# bt-programmer.net
KiCad netlist of a schematic drawn in EAGLE
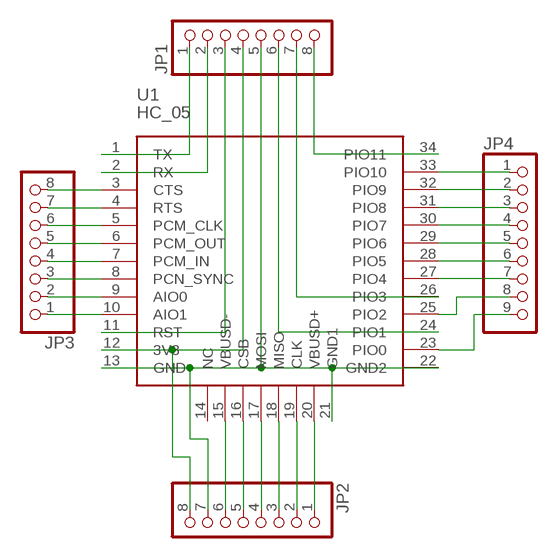
[diagram p0: schematic, sheet 1]

(export (version "E")
  (design (tool "Eeschema 10.0.6"))
  (components
    (comp (ref "JP1")
      (value "PINHD-1X8")
      (footprint "eagle-import:1X08")
      (libsource (lib "eagle-import") (part "PINHD-1X8"))
    )
    (comp (ref "JP2")
      (value "PINHD-1X8")
      (footprint "eagle-import:1X08")
      (libsource (lib "eagle-import") (part "PINHD-1X8"))
    )
    (comp (ref "JP3")
      (value "PINHD-1X8")
      (footprint "eagle-import:1X08")
      (libsource (lib "eagle-import") (part "PINHD-1X8"))
    )
    (comp (ref "JP4")
      (value "PINHD-1X9")
      (footprint "eagle-import:1X09")
      (libsource (lib "eagle-import") (part "PINHD-1X9"))
    )
    (comp (ref "U1")
      (value "HC_05")
      (footprint "eagle-import:BLUETOOTH_SMD")
      (libsource (lib "eagle-import") (part "HC_05"))
    )
  )
  (nets
    (net (code "1") (name "Net-(U1-3V3)") (class "Default")
      (node (ref "JP1") (pin "4") (pinfunction "4_4") (pintype "passive"))
      (node (ref "JP2") (pin "8") (pinfunction "8_8") (pintype "passive"))
      (node (ref "U1") (pin "12") (pinfunction "3V3_12") (pintype "bidirectional"))
    )
    (net (code "2") (name "Net-(U1-AIO0)") (class "Default")
      (node (ref "JP3") (pin "2") (pinfunction "2_2") (pintype "passive"))
      (node (ref "U1") (pin "9") (pinfunction "AIO0_9") (pintype "bidirectional"))
    )
    (net (code "3") (name "Net-(U1-AIO1)") (class "Default")
      (node (ref "JP3") (pin "1") (pinfunction "1_1") (pintype "passive"))
      (node (ref "U1") (pin "10") (pinfunction "AIO1_10") (pintype "bidirectional"))
    )
    (net (code "4") (name "Net-(U1-CLK)") (class "Default")
      (node (ref "JP2") (pin "2") (pinfunction "2_2") (pintype "passive"))
      (node (ref "U1") (pin "19") (pinfunction "CLK_19") (pintype "bidirectional"))
    )
    (net (code "5") (name "Net-(U1-CSB)") (class "Default")
      (node (ref "JP2") (pin "5") (pinfunction "5_5") (pintype "passive"))
      (node (ref "U1") (pin "16") (pinfunction "CSB_16") (pintype "bidirectional"))
    )
    (net (code "6") (name "Net-(U1-CTS)") (class "Default")
      (node (ref "JP3") (pin "8") (pinfunction "8_8") (pintype "passive"))
      (node (ref "U1") (pin "3") (pinfunction "CTS_3") (pintype "bidirectional"))
    )
    (net (code "7") (name "Net-(U1-GND)") (class "Default")
      (node (ref "JP1") (pin "5") (pinfunction "5_5") (pintype "passive"))
      (node (ref "JP2") (pin "7") (pinfunction "7_7") (pintype "passive"))
      (node (ref "U1") (pin "13") (pinfunction "GND_13") (pintype "bidirectional"))
      (node (ref "U1") (pin "21") (pinfunction "GND1_21") (pintype "bidirectional"))
      (node (ref "U1") (pin "22") (pinfunction "GND2_22") (pintype "bidirectional"))
    )
    (net (code "8") (name "Net-(U1-MISO)") (class "Default")
      (node (ref "JP2") (pin "3") (pinfunction "3_3") (pintype "passive"))
      (node (ref "U1") (pin "18") (pinfunction "MISO_18") (pintype "bidirectional"))
    )
    (net (code "9") (name "Net-(U1-MOSI)") (class "Default")
      (node (ref "JP2") (pin "4") (pinfunction "4_4") (pintype "passive"))
      (node (ref "U1") (pin "17") (pinfunction "MOSI_17") (pintype "bidirectional"))
    )
    (net (code "10") (name "Net-(U1-PCM_CLK)") (class "Default")
      (node (ref "JP3") (pin "6") (pinfunction "6_6") (pintype "passive"))
      (node (ref "U1") (pin "5") (pinfunction "PCM_CLK_5") (pintype "bidirectional"))
    )
    (net (code "11") (name "Net-(U1-PCM_IN)") (class "Default")
      (node (ref "JP3") (pin "4") (pinfunction "4_4") (pintype "passive"))
      (node (ref "U1") (pin "7") (pinfunction "PCM_IN_7") (pintype "bidirectional"))
    )
    (net (code "12") (name "Net-(U1-PCM_OUT)") (class "Default")
      (node (ref "JP3") (pin "5") (pinfunction "5_5") (pintype "passive"))
      (node (ref "U1") (pin "6") (pinfunction "PCM_OUT_6") (pintype "bidirectional"))
    )
    (net (code "13") (name "Net-(U1-PCN_SYNC)") (class "Default")
      (node (ref "JP3") (pin "3") (pinfunction "3_3") (pintype "passive"))
      (node (ref "U1") (pin "8") (pinfunction "PCN_SYNC_8") (pintype "bidirectional"))
    )
    (net (code "14") (name "Net-(U1-PIO0)") (class "Default")
      (node (ref "JP4") (pin "9") (pinfunction "9_9") (pintype "passive"))
      (node (ref "U1") (pin "23") (pinfunction "PIO0_23") (pintype "bidirectional"))
    )
    (net (code "15") (name "Net-(U1-PIO1)") (class "Default")
      (node (ref "JP1") (pin "6") (pinfunction "6_6") (pintype "passive"))
      (node (ref "U1") (pin "24") (pinfunction "PIO1_24") (pintype "bidirectional"))
    )
    (net (code "16") (name "Net-(U1-PIO2)") (class "Default")
      (node (ref "JP4") (pin "8") (pinfunction "8_8") (pintype "passive"))
      (node (ref "U1") (pin "25") (pinfunction "PIO2_25") (pintype "bidirectional"))
    )
    (net (code "17") (name "Net-(U1-PIO3)") (class "Default")
      (node (ref "JP1") (pin "7") (pinfunction "7_7") (pintype "passive"))
      (node (ref "U1") (pin "26") (pinfunction "PIO3_26") (pintype "bidirectional"))
    )
    (net (code "18") (name "Net-(U1-PIO4)") (class "Default")
      (node (ref "JP4") (pin "7") (pinfunction "7_7") (pintype "passive"))
      (node (ref "U1") (pin "27") (pinfunction "PIO4_27") (pintype "bidirectional"))
    )
    (net (code "19") (name "Net-(U1-PIO5)") (class "Default")
      (node (ref "JP4") (pin "6") (pinfunction "6_6") (pintype "passive"))
      (node (ref "U1") (pin "28") (pinfunction "PIO5_28") (pintype "bidirectional"))
    )
    (net (code "20") (name "Net-(U1-PIO6)") (class "Default")
      (node (ref "JP4") (pin "5") (pinfunction "5_5") (pintype "passive"))
      (node (ref "U1") (pin "29") (pinfunction "PIO6_29") (pintype "bidirectional"))
    )
    (net (code "21") (name "Net-(U1-PIO7)") (class "Default")
      (node (ref "JP4") (pin "4") (pinfunction "4_4") (pintype "passive"))
      (node (ref "U1") (pin "30") (pinfunction "PIO7_30") (pintype "bidirectional"))
    )
    (net (code "22") (name "Net-(U1-PIO8)") (class "Default")
      (node (ref "JP4") (pin "3") (pinfunction "3_3") (pintype "passive"))
      (node (ref "U1") (pin "31") (pinfunction "PIO8_31") (pintype "bidirectional"))
    )
    (net (code "23") (name "Net-(U1-PIO9)") (class "Default")
      (node (ref "JP4") (pin "2") (pinfunction "2_2") (pintype "passive"))
      (node (ref "U1") (pin "32") (pinfunction "PIO9_32") (pintype "bidirectional"))
    )
    (net (code "24") (name "Net-(U1-PIO10)") (class "Default")
      (node (ref "JP4") (pin "1") (pinfunction "1_1") (pintype "passive"))
      (node (ref "U1") (pin "33") (pinfunction "PIO10_33") (pintype "bidirectional"))
    )
    (net (code "25") (name "Net-(U1-PIO11)") (class "Default")
      (node (ref "JP1") (pin "8") (pinfunction "8_8") (pintype "passive"))
      (node (ref "U1") (pin "34") (pinfunction "PIO11_34") (pintype "bidirectional"))
    )
    (net (code "26") (name "Net-(U1-RST)") (class "Default")
      (node (ref "JP1") (pin "3") (pinfunction "3_3") (pintype "passive"))
      (node (ref "U1") (pin "11") (pinfunction "RST_11") (pintype "bidirectional"))
    )
    (net (code "27") (name "Net-(U1-RTS)") (class "Default")
      (node (ref "JP3") (pin "7") (pinfunction "7_7") (pintype "passive"))
      (node (ref "U1") (pin "4") (pinfunction "RTS_4") (pintype "bidirectional"))
    )
    (net (code "28") (name "Net-(U1-RX)") (class "Default")
      (node (ref "JP1") (pin "2") (pinfunction "2_2") (pintype "passive"))
      (node (ref "U1") (pin "2") (pinfunction "RX_2") (pintype "bidirectional"))
    )
    (net (code "29") (name "Net-(U1-TX)") (class "Default")
      (node (ref "JP1") (pin "1") (pinfunction "1_1") (pintype "passive"))
      (node (ref "U1") (pin "1") (pinfunction "TX_1") (pintype "bidirectional"))
    )
    (net (code "30") (name "Net-(U1-VBUSD+)") (class "Default")
      (node (ref "JP2") (pin "1") (pinfunction "1_1") (pintype "passive"))
      (node (ref "U1") (pin "20") (pinfunction "VBUSD+_20") (pintype "bidirectional"))
    )
    (net (code "31") (name "Net-(U1-VBUSD-)") (class "Default")
      (node (ref "JP2") (pin "6") (pinfunction "6_6") (pintype "passive"))
      (node (ref "U1") (pin "15") (pinfunction "VBUSD-_15") (pintype "bidirectional"))
    )
    (net (code "32") (name "unconnected-(U1-NC-Pad14)") (class "Default")
      (node (ref "U1") (pin "14") (pinfunction "NC_14") (pintype "bidirectional"))
    )
  )
)
